# SCH_Cowboy-key_2022-04-16.net
KiCad netlist of a schematic drawn in EasyEDA
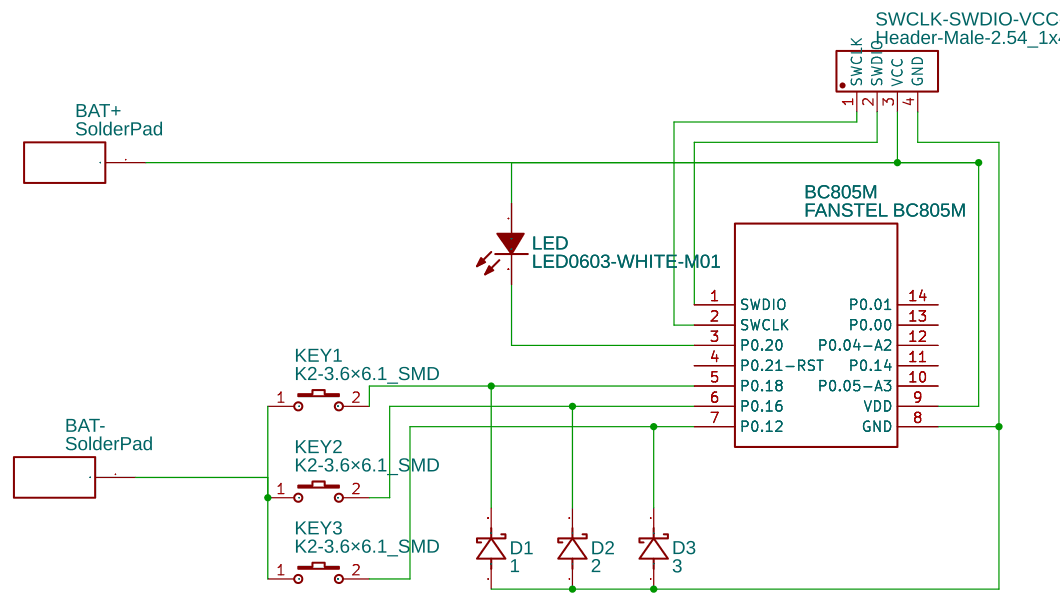
[diagram p0: schematic sheet]

(export (version "E")
  (design (tool "Eeschema 10.0.6"))
  (components
    (comp (ref "BAT+") (value "SolderPad") (libsource (lib "") (part "SolderPad")))
    (comp (ref "BAT-") (value "SolderPad") (libsource (lib "") (part "SolderPad_1")))
    (comp (ref "BC805M")
      (value "FANSTEL BC805M")
      (fields (field (name "BOM_Manufacturer Part") "BC805M"))
      (libsource (lib "") (part "FANSTEL BC805M"))
    )
    (comp (ref "D1")
      (value "1")
      (fields (field (name "BOM_Manufacturer Part") "1N4007") (field (name "BOM_Supplier Part") "C2892673"))
      (libsource (lib "") (part "1N4007_C2892673"))
    )
    (comp (ref "D2")
      (value "2")
      (fields (field (name "BOM_Manufacturer Part") "1N4007") (field (name "BOM_Supplier Part") "C2892673"))
      (libsource (lib "") (part "1N4007_C2892673"))
    )
    (comp (ref "D3")
      (value "3")
      (fields (field (name "BOM_Manufacturer Part") "1N4007") (field (name "BOM_Supplier Part") "C2892673"))
      (libsource (lib "") (part "1N4007_C2892673"))
    )
    (comp (ref "KEY1")
      (value "K2-3.6×6.1_SMD")
      (fields
        (field (name "BOM_Manufacturer Part") "K2-1107ST-A4SW-06")
        (field (name "BOM_Supplier Part") "C118141")
      )
      (libsource (lib "") (part "K2-3.6×6.1_SMD"))
    )
    (comp (ref "KEY2")
      (value "K2-3.6×6.1_SMD")
      (fields
        (field (name "BOM_Manufacturer Part") "K2-1107ST-A4SW-06")
        (field (name "BOM_Supplier Part") "C118141")
      )
      (libsource (lib "") (part "K2-3.6×6.1_SMD"))
    )
    (comp (ref "KEY3")
      (value "K2-3.6×6.1_SMD")
      (fields
        (field (name "BOM_Manufacturer Part") "K2-1107ST-A4SW-06")
        (field (name "BOM_Supplier Part") "C118141")
      )
      (libsource (lib "") (part "K2-3.6×6.1_SMD"))
    )
    (comp (ref "LED")
      (value "LED0603-WHITE-M01")
      (fields
        (field (name "BOM_Manufacturer Part") "LTW-C191TS5")
        (field (name "BOM_Supplier Part") "C125123")
      )
      (libsource (lib "") (part "LED0603-WHITE-M01"))
    )
    (comp (ref "SWCLK-SWDIO-VCC-GND")
      (value "Header-Male-2.54_1x4_C59481")
      (fields
        (field (name "BOM_Manufacturer Part") "Headers  Pins 1*4P")
        (field (name "BOM_Supplier Part") "C59481")
      )
      (libsource (lib "") (part "Header-Male-2.54_1x4_C59481"))
    )
  )
  (nets
    (net (code "1") (name "Net-(BAT--Pad1)") (class "Default")
      (node (ref "BAT-") (pin "1") (pinfunction "1_1") (pintype "unspecified"))
      (node (ref "KEY1") (pin "1") (pinfunction "1_1") (pintype "unspecified"))
      (node (ref "KEY2") (pin "1") (pinfunction "1_1") (pintype "unspecified"))
      (node (ref "KEY3") (pin "1") (pinfunction "1_1") (pintype "unspecified"))
    )
    (net (code "2") (name "Net-(BC805M-GND)") (class "Default")
      (node (ref "BC805M") (pin "8") (pinfunction "GND_8") (pintype "unspecified"))
      (node (ref "D1") (pin "1") (pinfunction "A_1") (pintype "unspecified"))
      (node (ref "D2") (pin "1") (pinfunction "A_1") (pintype "unspecified"))
      (node (ref "D3") (pin "1") (pinfunction "A_1") (pintype "unspecified"))
      (node (ref "SWCLK-SWDIO-VCC-GND") (pin "4") (pinfunction "GND_4") (pintype "unspecified"))
    )
    (net (code "3") (name "Net-(BC805M-P0.12)") (class "Default")
      (node (ref "BC805M") (pin "7") (pinfunction "P0.12_7") (pintype "unspecified"))
      (node (ref "D3") (pin "2") (pinfunction "K_2") (pintype "unspecified"))
      (node (ref "KEY3") (pin "2") (pinfunction "2_2") (pintype "unspecified"))
    )
    (net (code "4") (name "Net-(BC805M-P0.16)") (class "Default")
      (node (ref "BC805M") (pin "6") (pinfunction "P0.16_6") (pintype "unspecified"))
      (node (ref "D2") (pin "2") (pinfunction "K_2") (pintype "unspecified"))
      (node (ref "KEY2") (pin "2") (pinfunction "2_2") (pintype "unspecified"))
    )
    (net (code "5") (name "Net-(BC805M-P0.18)") (class "Default")
      (node (ref "BC805M") (pin "5") (pinfunction "P0.18_5") (pintype "unspecified"))
      (node (ref "D1") (pin "2") (pinfunction "K_2") (pintype "unspecified"))
      (node (ref "KEY1") (pin "2") (pinfunction "2_2") (pintype "unspecified"))
    )
    (net (code "6") (name "Net-(BC805M-P0.20)") (class "Default")
      (node (ref "BC805M") (pin "3") (pinfunction "P0.20_3") (pintype "unspecified"))
      (node (ref "LED") (pin "2") (pinfunction "K_2") (pintype "unspecified"))
    )
    (net (code "7") (name "Net-(BC805M-SWCLK)") (class "Default")
      (node (ref "BC805M") (pin "2") (pinfunction "SWCLK_2") (pintype "unspecified"))
      (node (ref "SWCLK-SWDIO-VCC-GND") (pin "1") (pinfunction "SWCLK_1") (pintype "unspecified"))
    )
    (net (code "8") (name "Net-(BC805M-SWDIO)") (class "Default")
      (node (ref "BC805M") (pin "1") (pinfunction "SWDIO_1") (pintype "unspecified"))
      (node (ref "SWCLK-SWDIO-VCC-GND") (pin "2") (pinfunction "SWDIO_2") (pintype "unspecified"))
    )
    (net (code "9") (name "Net-(BC805M-VDD)") (class "Default")
      (node (ref "BAT+") (pin "1") (pinfunction "1_1") (pintype "unspecified"))
      (node (ref "BC805M") (pin "9") (pinfunction "VDD_9") (pintype "unspecified"))
      (node (ref "LED") (pin "1") (pinfunction "A_1") (pintype "unspecified"))
      (node (ref "SWCLK-SWDIO-VCC-GND") (pin "3") (pinfunction "VCC_3") (pintype "unspecified"))
    )
    (net (code "10") (name "unconnected-(BC805M-P0.00-Pad13)") (class "Default")
      (node (ref "BC805M") (pin "13") (pinfunction "P0.00_13") (pintype "unspecified"))
    )
    (net (code "11") (name "unconnected-(BC805M-P0.01-Pad14)") (class "Default")
      (node (ref "BC805M") (pin "14") (pinfunction "P0.01_14") (pintype "unspecified"))
    )
    (net (code "12") (name "unconnected-(BC805M-P0.04-A2-Pad12)") (class "Default")
      (node (ref "BC805M") (pin "12") (pinfunction "P0.04-A2_12") (pintype "unspecified"))
    )
    (net (code "13") (name "unconnected-(BC805M-P0.05-A3-Pad10)") (class "Default")
      (node (ref "BC805M") (pin "10") (pinfunction "P0.05-A3_10") (pintype "unspecified"))
    )
    (net (code "14") (name "unconnected-(BC805M-P0.14-Pad11)") (class "Default")
      (node (ref "BC805M") (pin "11") (pinfunction "P0.14_11") (pintype "unspecified"))
    )
    (net (code "15") (name "unconnected-(BC805M-P0.21-RST-Pad4)") (class "Default")
      (node (ref "BC805M") (pin "4") (pinfunction "P0.21-RST_4") (pintype "unspecified"))
    )
  )
)
